# nm_npu_proc.net
KiCad netlist of a schematic drawn in Altium Designer
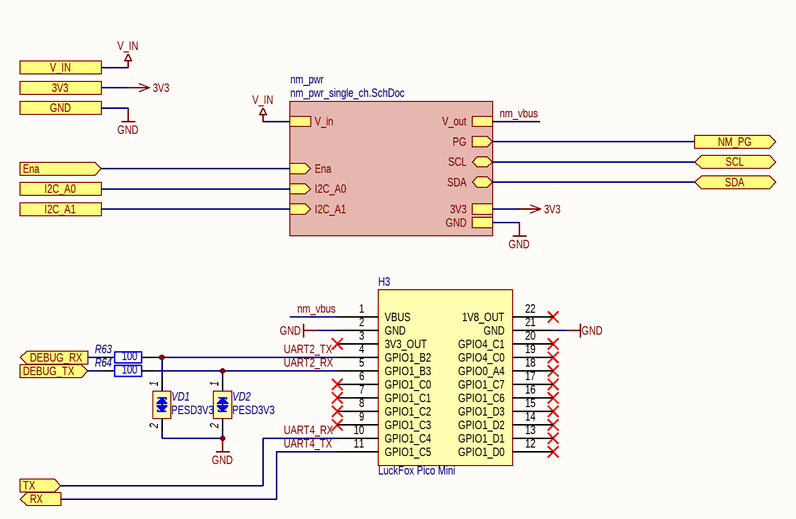
[diagram p0: nm_npu_proc.SchDoc]

(export (version "E")
  (design (tool "Eeschema 10.0.6"))
  (components
    (comp (ref "H3")
      (value "LuckFox Pico Mini")
      (footprint "DS1021-1x20")
      (libsource (lib "DS1021-1x20") (part "DS1021-1x20"))
    )
    (comp (ref "R63")
      (value "100")
      (footprint "SMD_0603")
      (description "Resistor")
      (libsource (lib "Passive") (part "Resistor"))
    )
    (comp (ref "R64")
      (value "100")
      (footprint "SMD_0603")
      (description "Resistor")
      (libsource (lib "Passive") (part "Resistor"))
    )
    (comp (ref "VD1")
      (value "PESD3V3")
      (footprint "SOD-323")
      (description "Low capacitance bidirectional ESD protection diodes")
      (libsource (lib "Diod") (part "PESDxL1BA"))
    )
    (comp (ref "VD2")
      (value "PESD3V3")
      (footprint "SOD-323")
      (description "Low capacitance bidirectional ESD protection diodes")
      (libsource (lib "Diod") (part "PESDxL1BA"))
    )
  )
  (nets
    (net (code "1") (name "/DEBUG_RX") (class "Default")
      (node (ref "R63") (pin "1") (pinfunction "1_1") (pintype "passive"))
    )
    (net (code "2") (name "/DEBUG_TX") (class "Default")
      (node (ref "R64") (pin "1") (pinfunction "1_1") (pintype "passive"))
    )
    (net (code "9") (name "/UART2_RX") (class "Default")
      (node (ref "H3") (pin "5") (pinfunction "GPIO1_B3_5") (pintype "passive"))
      (node (ref "R64") (pin "2") (pinfunction "2_2") (pintype "passive"))
      (node (ref "VD2") (pin "1") (pinfunction "cathode_1_1") (pintype "passive"))
    )
    (net (code "10") (name "/UART2_TX") (class "Default")
      (node (ref "H3") (pin "4") (pinfunction "GPIO1_B2_4") (pintype "passive"))
      (node (ref "R63") (pin "2") (pinfunction "2_2") (pintype "passive"))
      (node (ref "VD1") (pin "1") (pinfunction "cathode_1_1") (pintype "passive"))
    )
    (net (code "11") (name "/UART4_RX") (class "Default")
      (node (ref "H3") (pin "10") (pinfunction "GPIO1_C4_10") (pintype "passive"))
    )
    (net (code "12") (name "/UART4_TX") (class "Default")
      (node (ref "H3") (pin "11") (pinfunction "GPIO1_C5_11") (pintype "passive"))
    )
    (net (code "13") (name "/nm_vbus") (class "Default")
      (node (ref "H3") (pin "1") (pinfunction "VBUS_1") (pintype "power_in"))
    )
    (net (code "15") (name "GND") (class "Default")
      (node (ref "H3") (pin "2") (pinfunction "GND_2") (pintype "power_in"))
      (node (ref "H3") (pin "21") (pinfunction "GND_21") (pintype "power_in"))
      (node (ref "VD1") (pin "2") (pinfunction "cathode_2_2") (pintype "passive"))
      (node (ref "VD2") (pin "2") (pinfunction "cathode_2_2") (pintype "passive"))
    )
    (net (code "17") (name "unconnected-(H3-1V8_OUT-Pad22)") (class "Default")
      (node (ref "H3") (pin "22") (pinfunction "1V8_OUT_22") (pintype "power_in+no_connect"))
    )
    (net (code "18") (name "unconnected-(H3-3V3_OUT-Pad3)") (class "Default")
      (node (ref "H3") (pin "3") (pinfunction "3V3_OUT_3") (pintype "power_in+no_connect"))
    )
    (net (code "19") (name "unconnected-(H3-GPIO0_A4-Pad18)") (class "Default")
      (node (ref "H3") (pin "18") (pinfunction "GPIO0_A4_18") (pintype "passive+no_connect"))
    )
    (net (code "20") (name "unconnected-(H3-GPIO1_C0-Pad6)") (class "Default")
      (node (ref "H3") (pin "6") (pinfunction "GPIO1_C0_6") (pintype "passive+no_connect"))
    )
    (net (code "21") (name "unconnected-(H3-GPIO1_C1-Pad7)") (class "Default")
      (node (ref "H3") (pin "7") (pinfunction "GPIO1_C1_7") (pintype "passive+no_connect"))
    )
    (net (code "22") (name "unconnected-(H3-GPIO1_C2-Pad8)") (class "Default")
      (node (ref "H3") (pin "8") (pinfunction "GPIO1_C2_8") (pintype "passive+no_connect"))
    )
    (net (code "23") (name "unconnected-(H3-GPIO1_C3-Pad9)") (class "Default")
      (node (ref "H3") (pin "9") (pinfunction "GPIO1_C3_9") (pintype "passive+no_connect"))
    )
    (net (code "24") (name "unconnected-(H3-GPIO1_C6-Pad16)") (class "Default")
      (node (ref "H3") (pin "16") (pinfunction "GPIO1_C6_16") (pintype "passive+no_connect"))
    )
    (net (code "25") (name "unconnected-(H3-GPIO1_C7-Pad17)") (class "Default")
      (node (ref "H3") (pin "17") (pinfunction "GPIO1_C7_17") (pintype "passive+no_connect"))
    )
    (net (code "26") (name "unconnected-(H3-GPIO1_D0-Pad12)") (class "Default")
      (node (ref "H3") (pin "12") (pinfunction "GPIO1_D0_12") (pintype "passive+no_connect"))
    )
    (net (code "27") (name "unconnected-(H3-GPIO1_D1-Pad13)") (class "Default")
      (node (ref "H3") (pin "13") (pinfunction "GPIO1_D1_13") (pintype "passive+no_connect"))
    )
    (net (code "28") (name "unconnected-(H3-GPIO1_D2-Pad14)") (class "Default")
      (node (ref "H3") (pin "14") (pinfunction "GPIO1_D2_14") (pintype "passive+no_connect"))
    )
    (net (code "29") (name "unconnected-(H3-GPIO1_D3-Pad15)") (class "Default")
      (node (ref "H3") (pin "15") (pinfunction "GPIO1_D3_15") (pintype "passive+no_connect"))
    )
    (net (code "30") (name "unconnected-(H3-GPIO4_C0-Pad19)") (class "Default")
      (node (ref "H3") (pin "19") (pinfunction "GPIO4_C0_19") (pintype "passive+no_connect"))
    )
    (net (code "31") (name "unconnected-(H3-GPIO4_C1-Pad20)") (class "Default")
      (node (ref "H3") (pin "20") (pinfunction "GPIO4_C1_20") (pintype "passive+no_connect"))
    )
  )
)
